# inverter.net
KiCad netlist of a schematic drawn in Altium Designer
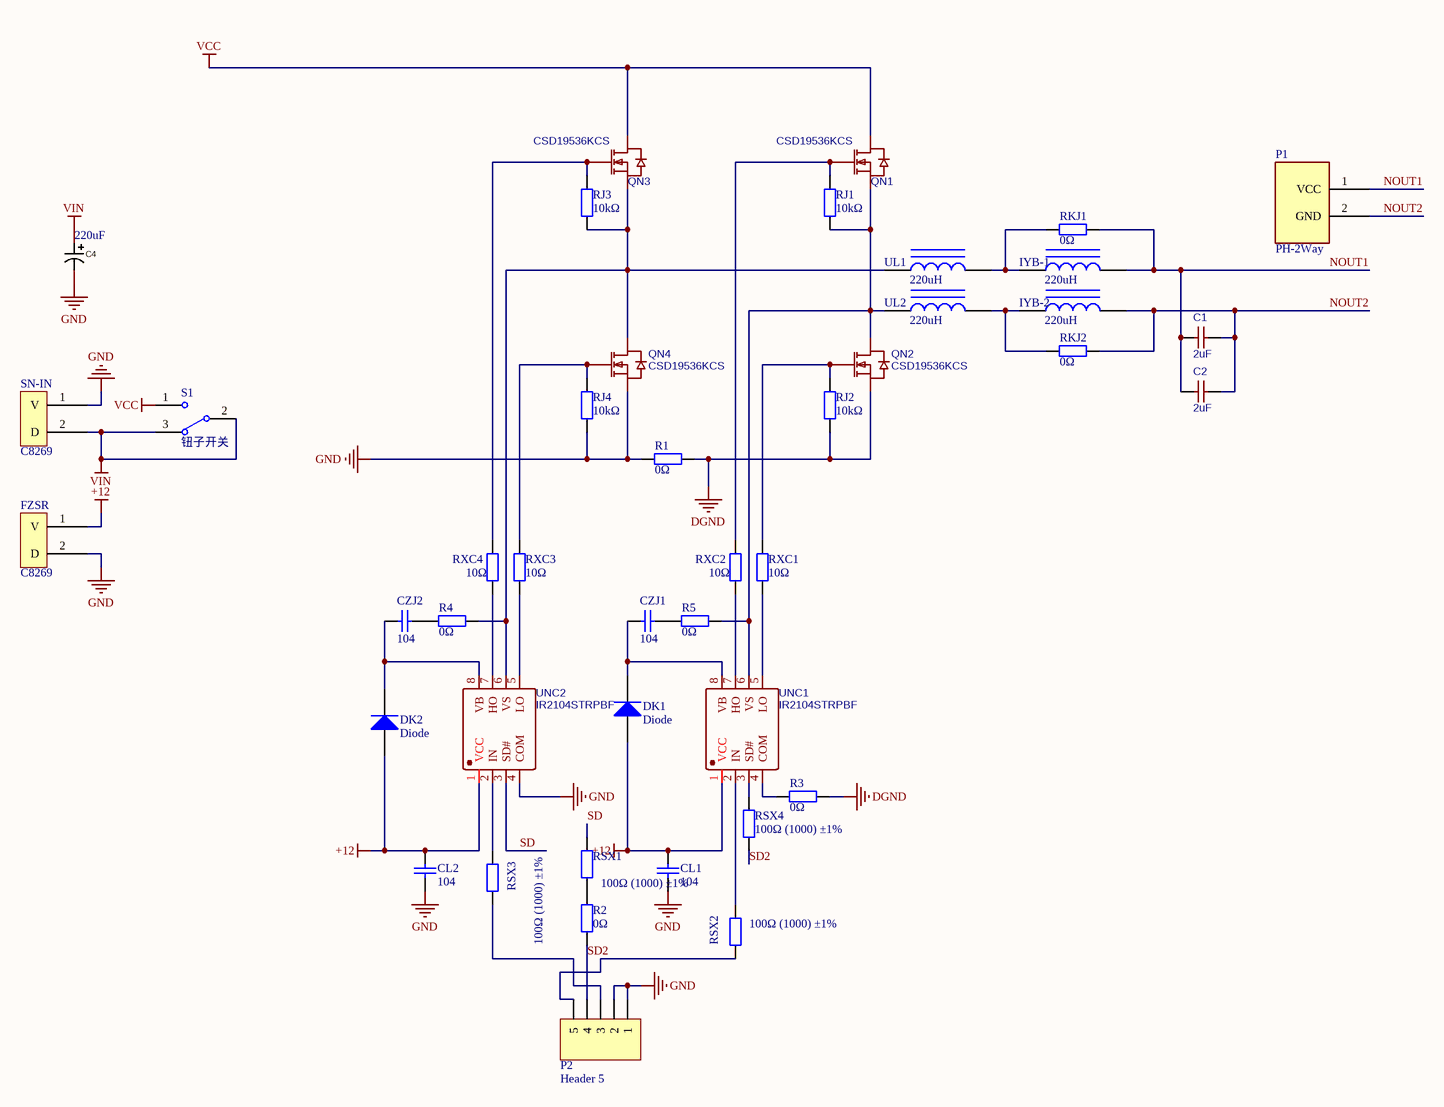
[diagram p0: inverter.SchDoc]

(export (version "E")
  (design (tool "Eeschema 10.0.6"))
  (components
    (comp (ref "C1")
      (value "2uF")
      (footprint "CAP-TH_L23.0-W10.0-P20.00-D1.4")
      (description "CBB，2uF电容")
      (fields
        (field (name "BOM_MANUFACTURER PART") "MPP205J4241119LC")
        (field (name "BOM_SUPPLIER PART") "C93266")
      )
      (libsource (lib "Schlib1") (part "2uF-CBB"))
    )
    (comp (ref "C2")
      (value "2uF")
      (footprint "CAP-TH_L23.0-W10.0-P20.00-D1.4")
      (description "CBB，2uF电容")
      (fields
        (field (name "BOM_MANUFACTURER PART") "MPP205J4241119LC")
        (field (name "BOM_SUPPLIER PART") "C93266")
      )
      (libsource (lib "Schlib1") (part "2uF-CBB"))
    )
    (comp (ref "C4")
      (value "220uF")
      (footprint "CAP 5.0*10*12.5-H")
      (description "插件电容")
      (fields
        (field (name "MANUFACTURER") "MAN YUE(万裕科技)")
        (field (name "MANUFACTURER PART") "ULR107M1CE08TUX0CR")
      )
      (libsource (lib "SFerret") (part "TH_Cap"))
    )
    (comp (ref "CL1")
      (value "104")
      (footprint "0603_C")
      (description "贴片电容")
      (libsource (lib "SFerret") (part "SMT_Cap"))
    )
    (comp (ref "CL2")
      (value "104")
      (footprint "0603_C")
      (description "贴片电容")
      (libsource (lib "SFerret") (part "SMT_Cap"))
    )
    (comp (ref "CZJ1")
      (value "104")
      (footprint "0603_C")
      (description "贴片电容")
      (libsource (lib "SFerret") (part "SMT_Cap"))
    )
    (comp (ref "CZJ2")
      (value "104")
      (footprint "0603_C")
      (description "贴片电容")
      (libsource (lib "SFerret") (part "SMT_Cap"))
    )
    (comp (ref "DK1")
      (value "Diode")
      (footprint "SMA(DO-214AC)_S2")
      (description "通用二极管")
      (libsource (lib "SFerret") (part "Diode"))
    )
    (comp (ref "DK2")
      (value "Diode")
      (footprint "SMA(DO-214AC)_S2")
      (description "通用二极管")
      (libsource (lib "SFerret") (part "Diode"))
    )
    (comp (ref "FZSR") (value "C8269") (footprint "C8269") (libsource (lib "Schlib1") (part "C8269")))
    (comp (ref "IYB-1")
      (value "220uH")
      (footprint "CDRH127")
      (description "功率电感")
      (libsource (lib "SFerret") (part "SMT_Iud_Power"))
    )
    (comp (ref "IYB-2")
      (value "220uH")
      (footprint "CDRH127")
      (description "功率电感")
      (libsource (lib "SFerret") (part "SMT_Iud_Power"))
    )
    (comp (ref "P1")
      (value "PH-2Way")
      (footprint "XH2.54-WS-2P")
      (libsource (lib "SFerret") (part "PH-2Way"))
    )
    (comp (ref "P2")
      (value "Header 5")
      (footprint "HDR2.54-WS-5P")
      (description "排针")
      (libsource (lib "SFerret") (part "Header 5"))
    )
    (comp (ref "QN1")
      (value "CSD19536KCS")
      (footprint "TO-220-3_L10.0-W4.5-P2.54-L")
      (description "实验室现有NMOS")
      (fields (field (name "BOM_SUPPLIER PART") "C206030") (field (name "CONTRIBUTOR") "LCSC"))
      (libsource (lib "Schlib1") (part "CSD19536KCS"))
    )
    (comp (ref "QN2")
      (value "CSD19536KCS")
      (footprint "TO-220-3_L10.0-W4.5-P2.54-L")
      (description "实验室现有NMOS")
      (fields (field (name "BOM_SUPPLIER PART") "C206030") (field (name "CONTRIBUTOR") "LCSC"))
      (libsource (lib "Schlib1") (part "CSD19536KCS"))
    )
    (comp (ref "QN3")
      (value "CSD19536KCS")
      (footprint "TO-220-3_L10.0-W4.5-P2.54-L")
      (description "实验室现有NMOS")
      (fields (field (name "BOM_SUPPLIER PART") "C206030") (field (name "CONTRIBUTOR") "LCSC"))
      (libsource (lib "Schlib1") (part "CSD19536KCS"))
    )
    (comp (ref "QN4")
      (value "CSD19536KCS")
      (footprint "TO-220-3_L10.0-W4.5-P2.54-L")
      (description "实验室现有NMOS")
      (fields (field (name "BOM_SUPPLIER PART") "C206030") (field (name "CONTRIBUTOR") "LCSC"))
      (libsource (lib "Schlib1") (part "CSD19536KCS"))
    )
    (comp (ref "R1")
      (value "0Ω")
      (footprint "1206_R")
      (description "贴片电阻")
      (libsource (lib "") (part "SMT_Res_2"))
    )
    (comp (ref "R2")
      (value "0Ω")
      (footprint "1206_R")
      (description "贴片电阻")
      (libsource (lib "") (part "SMT_Res_3"))
    )
    (comp (ref "R3")
      (value "0Ω")
      (footprint "1206_R")
      (description "贴片电阻")
      (libsource (lib "") (part "SMT_Res_1"))
    )
    (comp (ref "R4")
      (value "0Ω")
      (footprint "1206_R")
      (description "贴片电阻")
      (libsource (lib "") (part "SMT_Res_1"))
    )
    (comp (ref "R5")
      (value "0Ω")
      (footprint "1206_R")
      (description "贴片电阻")
      (libsource (lib "") (part "SMT_Res_1"))
    )
    (comp (ref "RJ1")
      (value "10kΩ")
      (footprint "0603_R")
      (description "贴片电阻")
      (libsource (lib "SFerret") (part "SMT_Res"))
    )
    (comp (ref "RJ2")
      (value "10kΩ")
      (footprint "0603_R")
      (description "贴片电阻")
      (libsource (lib "SFerret") (part "SMT_Res"))
    )
    (comp (ref "RJ3")
      (value "10kΩ")
      (footprint "0603_R")
      (description "贴片电阻")
      (libsource (lib "SFerret") (part "SMT_Res"))
    )
    (comp (ref "RJ4")
      (value "10kΩ")
      (footprint "0603_R")
      (description "贴片电阻")
      (libsource (lib "SFerret") (part "SMT_Res"))
    )
    (comp (ref "RKJ1")
      (value "0Ω")
      (footprint "1206_R")
      (description "贴片电阻")
      (libsource (lib "") (part "SMT_Res_1"))
    )
    (comp (ref "RKJ2")
      (value "0Ω")
      (footprint "1206_R")
      (description "贴片电阻")
      (libsource (lib "") (part "SMT_Res_1"))
    )
    (comp (ref "RSX1")
      (value "100Ω (1000) ±1%")
      (footprint "0805_R")
      (description "贴片电阻")
      (libsource (lib "RES") (part "0805 100Ω (1000) 1%"))
    )
    (comp (ref "RSX2")
      (value "100Ω (1000) ±1%")
      (footprint "0805_R")
      (description "贴片电阻")
      (libsource (lib "RES") (part "0805 100Ω (1000) 1%"))
    )
    (comp (ref "RSX3")
      (value "100Ω (1000) ±1%")
      (footprint "0805_R")
      (description "贴片电阻")
      (libsource (lib "RES") (part "0805 100Ω (1000) 1%"))
    )
    (comp (ref "RSX4")
      (value "100Ω (1000) ±1%")
      (footprint "0805_R")
      (description "贴片电阻")
      (libsource (lib "RES") (part "0805 100Ω (1000) 1%"))
    )
    (comp (ref "RXC1")
      (value "10Ω")
      (footprint "0603_R")
      (description "贴片电阻")
      (libsource (lib "SFerret") (part "SMT_Res"))
    )
    (comp (ref "RXC2")
      (value "10Ω")
      (footprint "0603_R")
      (description "贴片电阻")
      (libsource (lib "SFerret") (part "SMT_Res"))
    )
    (comp (ref "RXC3")
      (value "10Ω")
      (footprint "0603_R")
      (description "贴片电阻")
      (libsource (lib "SFerret") (part "SMT_Res"))
    )
    (comp (ref "RXC4")
      (value "10Ω")
      (footprint "0603_R")
      (description "贴片电阻")
      (libsource (lib "SFerret") (part "SMT_Res"))
    )
    (comp (ref "S1")
      (value "钮子开关")
      (footprint "SS-12D10")
      (description "大功率开关")
      (libsource (lib "SFerret") (part "钮子开关"))
    )
    (comp (ref "SN-IN") (value "C8269") (footprint "C8269") (libsource (lib "Schlib1") (part "C8269")))
    (comp (ref "UL1")
      (value "220uH")
      (footprint "CDRH127")
      (description "功率电感")
      (libsource (lib "SFerret") (part "SMT_Iud_Power"))
    )
    (comp (ref "UL2")
      (value "220uH")
      (footprint "CDRH127")
      (description "功率电感")
      (libsource (lib "SFerret") (part "SMT_Iud_Power"))
    )
    (comp (ref "UNC1")
      (value "IR2104STRPBF")
      (footprint "SOIC-8_L4.9-W3.9-P1.27-LS6.0-BL")
      (description "贴片IR2104封装")
      (fields (field (name "BOM_SUPPLIER PART") "C2960"))
      (libsource (lib "Schlib1") (part "IR2104STRPBF"))
    )
    (comp (ref "UNC2")
      (value "IR2104STRPBF")
      (footprint "SOIC-8_L4.9-W3.9-P1.27-LS6.0-BL")
      (description "贴片IR2104封装")
      (fields (field (name "BOM_SUPPLIER PART") "C2960"))
      (libsource (lib "Schlib1") (part "IR2104STRPBF"))
    )
  )
  (nets
    (net (code "1") (name "+12") (class "Default")
      (node (ref "CL1") (pin "2") (pinfunction "2_2") (pintype "passive"))
      (node (ref "CL2") (pin "2") (pinfunction "2_2") (pintype "passive"))
      (node (ref "DK1") (pin "1") (pinfunction "A_1") (pintype "passive"))
      (node (ref "DK2") (pin "1") (pinfunction "A_1") (pintype "passive"))
      (node (ref "FZSR") (pin "1") (pinfunction "V_1") (pintype "passive"))
      (node (ref "UNC1") (pin "1") (pinfunction "VCC_1") (pintype "passive"))
      (node (ref "UNC2") (pin "1") (pinfunction "VCC_1") (pintype "passive"))
    )
    (net (code "2") (name "/NOUT1") (class "Default")
      (node (ref "C1") (pin "1") (pinfunction "1_1") (pintype "passive"))
      (node (ref "C2") (pin "1") (pinfunction "1_1") (pintype "passive"))
      (node (ref "IYB-1") (pin "2") (pinfunction "2_2") (pintype "passive"))
      (node (ref "P1") (pin "1") (pinfunction "VCC_1") (pintype "passive"))
      (node (ref "RKJ1") (pin "2") (pinfunction "2_2") (pintype "passive"))
    )
    (net (code "3") (name "/NOUT2") (class "Default")
      (node (ref "C1") (pin "2") (pinfunction "2_2") (pintype "passive"))
      (node (ref "C2") (pin "2") (pinfunction "2_2") (pintype "passive"))
      (node (ref "IYB-2") (pin "2") (pinfunction "2_2") (pintype "passive"))
      (node (ref "P1") (pin "2") (pinfunction "GND_2") (pintype "passive"))
      (node (ref "RKJ2") (pin "2") (pinfunction "2_2") (pintype "passive"))
    )
    (net (code "4") (name "/SD") (class "Default")
      (node (ref "RSX1") (pin "2") (pinfunction "2_2") (pintype "passive"))
      (node (ref "UNC2") (pin "3") (pinfunction "SD#_3") (pintype "passive"))
    )
    (net (code "5") (name "/SD2") (class "Default")
      (node (ref "P2") (pin "4") (pinfunction "4_4") (pintype "passive"))
      (node (ref "R2") (pin "2") (pinfunction "2_2") (pintype "passive"))
      (node (ref "RSX4") (pin "1") (pinfunction "1_1") (pintype "passive"))
    )
    (net (code "6") (name "DGND") (class "Default")
      (node (ref "QN2") (pin "3") (pinfunction "S_3") (pintype "passive"))
      (node (ref "R1") (pin "1") (pinfunction "1_1") (pintype "passive"))
      (node (ref "R3") (pin "2") (pinfunction "2_2") (pintype "passive"))
      (node (ref "RJ2") (pin "1") (pinfunction "1_1") (pintype "passive"))
    )
    (net (code "7") (name "GND") (class "Default")
      (node (ref "C4") (pin "2") (pinfunction "2_2") (pintype "passive"))
      (node (ref "CL1") (pin "1") (pinfunction "1_1") (pintype "passive"))
      (node (ref "CL2") (pin "1") (pinfunction "1_1") (pintype "passive"))
      (node (ref "FZSR") (pin "2") (pinfunction "D_2") (pintype "passive"))
      (node (ref "P2") (pin "1") (pinfunction "1_1") (pintype "passive"))
      (node (ref "P2") (pin "2") (pinfunction "2_2") (pintype "passive"))
      (node (ref "QN4") (pin "3") (pinfunction "S_3") (pintype "passive"))
      (node (ref "R1") (pin "2") (pinfunction "2_2") (pintype "passive"))
      (node (ref "RJ4") (pin "1") (pinfunction "1_1") (pintype "passive"))
      (node (ref "SN-IN") (pin "1") (pinfunction "V_1") (pintype "passive"))
      (node (ref "UNC2") (pin "4") (pinfunction "COM_4") (pintype "passive"))
    )
    (net (code "8") (name "Net-(CZJ1-Pad2)") (class "Default")
      (node (ref "CZJ1") (pin "2") (pinfunction "2_2") (pintype "passive"))
      (node (ref "R5") (pin "1") (pinfunction "1_1") (pintype "passive"))
    )
    (net (code "9") (name "Net-(CZJ2-Pad2)") (class "Default")
      (node (ref "CZJ2") (pin "2") (pinfunction "2_2") (pintype "passive"))
      (node (ref "R4") (pin "1") (pinfunction "1_1") (pintype "passive"))
    )
    (net (code "10") (name "Net-(DK1-K)") (class "Default")
      (node (ref "CZJ1") (pin "1") (pinfunction "1_1") (pintype "passive"))
      (node (ref "DK1") (pin "2") (pinfunction "K_2") (pintype "passive"))
      (node (ref "UNC1") (pin "8") (pinfunction "VB_8") (pintype "passive"))
    )
    (net (code "11") (name "Net-(DK2-K)") (class "Default")
      (node (ref "CZJ2") (pin "1") (pinfunction "1_1") (pintype "passive"))
      (node (ref "DK2") (pin "2") (pinfunction "K_2") (pintype "passive"))
      (node (ref "UNC2") (pin "8") (pinfunction "VB_8") (pintype "passive"))
    )
    (net (code "12") (name "Net-(IYB-1-Pad1)") (class "Default")
      (node (ref "IYB-1") (pin "1") (pinfunction "1_1") (pintype "passive"))
      (node (ref "RKJ1") (pin "1") (pinfunction "1_1") (pintype "passive"))
      (node (ref "UL1") (pin "2") (pinfunction "2_2") (pintype "passive"))
    )
    (net (code "13") (name "Net-(IYB-2-Pad1)") (class "Default")
      (node (ref "IYB-2") (pin "1") (pinfunction "1_1") (pintype "passive"))
      (node (ref "RKJ2") (pin "1") (pinfunction "1_1") (pintype "passive"))
      (node (ref "UL2") (pin "2") (pinfunction "2_2") (pintype "passive"))
    )
    (net (code "14") (name "Net-(P2-Pad3)") (class "Default")
      (node (ref "P2") (pin "3") (pinfunction "3_3") (pintype "passive"))
      (node (ref "RSX3") (pin "1") (pinfunction "1_1") (pintype "passive"))
    )
    (net (code "15") (name "Net-(P2-Pad5)") (class "Default")
      (node (ref "P2") (pin "5") (pinfunction "5_5") (pintype "passive"))
      (node (ref "RSX2") (pin "1") (pinfunction "1_1") (pintype "passive"))
    )
    (net (code "16") (name "Net-(QN1-G)") (class "Default")
      (node (ref "QN1") (pin "1") (pinfunction "G_1") (pintype "passive"))
      (node (ref "RJ1") (pin "2") (pinfunction "2_2") (pintype "passive"))
      (node (ref "RXC2") (pin "2") (pinfunction "2_2") (pintype "passive"))
    )
    (net (code "17") (name "Net-(QN1-S)") (class "Default")
      (node (ref "QN1") (pin "3") (pinfunction "S_3") (pintype "passive"))
      (node (ref "QN2") (pin "2") (pinfunction "D_2") (pintype "passive"))
      (node (ref "R5") (pin "2") (pinfunction "2_2") (pintype "passive"))
      (node (ref "RJ1") (pin "1") (pinfunction "1_1") (pintype "passive"))
      (node (ref "UL2") (pin "1") (pinfunction "1_1") (pintype "passive"))
      (node (ref "UNC1") (pin "6") (pinfunction "VS_6") (pintype "passive"))
    )
    (net (code "18") (name "Net-(QN2-G)") (class "Default")
      (node (ref "QN2") (pin "1") (pinfunction "G_1") (pintype "passive"))
      (node (ref "RJ2") (pin "2") (pinfunction "2_2") (pintype "passive"))
      (node (ref "RXC1") (pin "2") (pinfunction "2_2") (pintype "passive"))
    )
    (net (code "19") (name "Net-(QN3-G)") (class "Default")
      (node (ref "QN3") (pin "1") (pinfunction "G_1") (pintype "passive"))
      (node (ref "RJ3") (pin "2") (pinfunction "2_2") (pintype "passive"))
      (node (ref "RXC4") (pin "2") (pinfunction "2_2") (pintype "passive"))
    )
    (net (code "20") (name "Net-(QN3-S)") (class "Default")
      (node (ref "QN3") (pin "3") (pinfunction "S_3") (pintype "passive"))
      (node (ref "QN4") (pin "2") (pinfunction "D_2") (pintype "passive"))
      (node (ref "R4") (pin "2") (pinfunction "2_2") (pintype "passive"))
      (node (ref "RJ3") (pin "1") (pinfunction "1_1") (pintype "passive"))
      (node (ref "UL1") (pin "1") (pinfunction "1_1") (pintype "passive"))
      (node (ref "UNC2") (pin "6") (pinfunction "VS_6") (pintype "passive"))
    )
    (net (code "21") (name "Net-(QN4-G)") (class "Default")
      (node (ref "QN4") (pin "1") (pinfunction "G_1") (pintype "passive"))
      (node (ref "RJ4") (pin "2") (pinfunction "2_2") (pintype "passive"))
      (node (ref "RXC3") (pin "2") (pinfunction "2_2") (pintype "passive"))
    )
    (net (code "22") (name "Net-(R2-Pad1)") (class "Default")
      (node (ref "R2") (pin "1") (pinfunction "1_1") (pintype "passive"))
      (node (ref "RSX1") (pin "1") (pinfunction "1_1") (pintype "passive"))
    )
    (net (code "23") (name "Net-(UNC1-COM)") (class "Default")
      (node (ref "R3") (pin "1") (pinfunction "1_1") (pintype "passive"))
      (node (ref "UNC1") (pin "4") (pinfunction "COM_4") (pintype "passive"))
    )
    (net (code "24") (name "Net-(UNC1-HO)") (class "Default")
      (node (ref "RXC2") (pin "1") (pinfunction "1_1") (pintype "passive"))
      (node (ref "UNC1") (pin "7") (pinfunction "HO_7") (pintype "passive"))
    )
    (net (code "25") (name "Net-(UNC1-IN)") (class "Default")
      (node (ref "RSX2") (pin "2") (pinfunction "2_2") (pintype "passive"))
      (node (ref "UNC1") (pin "2") (pinfunction "IN_2") (pintype "passive"))
    )
    (net (code "26") (name "Net-(UNC1-LO)") (class "Default")
      (node (ref "RXC1") (pin "1") (pinfunction "1_1") (pintype "passive"))
      (node (ref "UNC1") (pin "5") (pinfunction "LO_5") (pintype "passive"))
    )
    (net (code "27") (name "Net-(UNC1-SD#)") (class "Default")
      (node (ref "RSX4") (pin "2") (pinfunction "2_2") (pintype "passive"))
      (node (ref "UNC1") (pin "3") (pinfunction "SD#_3") (pintype "passive"))
    )
    (net (code "28") (name "Net-(UNC2-HO)") (class "Default")
      (node (ref "RXC4") (pin "1") (pinfunction "1_1") (pintype "passive"))
      (node (ref "UNC2") (pin "7") (pinfunction "HO_7") (pintype "passive"))
    )
    (net (code "29") (name "Net-(UNC2-IN)") (class "Default")
      (node (ref "RSX3") (pin "2") (pinfunction "2_2") (pintype "passive"))
      (node (ref "UNC2") (pin "2") (pinfunction "IN_2") (pintype "passive"))
    )
    (net (code "30") (name "Net-(UNC2-LO)") (class "Default")
      (node (ref "RXC3") (pin "1") (pinfunction "1_1") (pintype "passive"))
      (node (ref "UNC2") (pin "5") (pinfunction "LO_5") (pintype "passive"))
    )
    (net (code "31") (name "VCC") (class "Default")
      (node (ref "QN1") (pin "2") (pinfunction "D_2") (pintype "passive"))
      (node (ref "QN3") (pin "2") (pinfunction "D_2") (pintype "passive"))
      (node (ref "S1") (pin "1") (pinfunction "1_1") (pintype "passive"))
    )
    (net (code "32") (name "VIN") (class "Default")
      (node (ref "C4") (pin "1") (pinfunction "1_1") (pintype "passive"))
      (node (ref "S1") (pin "2") (pinfunction "2_2") (pintype "passive"))
      (node (ref "S1") (pin "3") (pinfunction "3_3") (pintype "passive"))
      (node (ref "SN-IN") (pin "2") (pinfunction "D_2") (pintype "passive"))
    )
  )
)
